# ATmega328p.net
KiCad netlist of a schematic drawn in Altium Designer
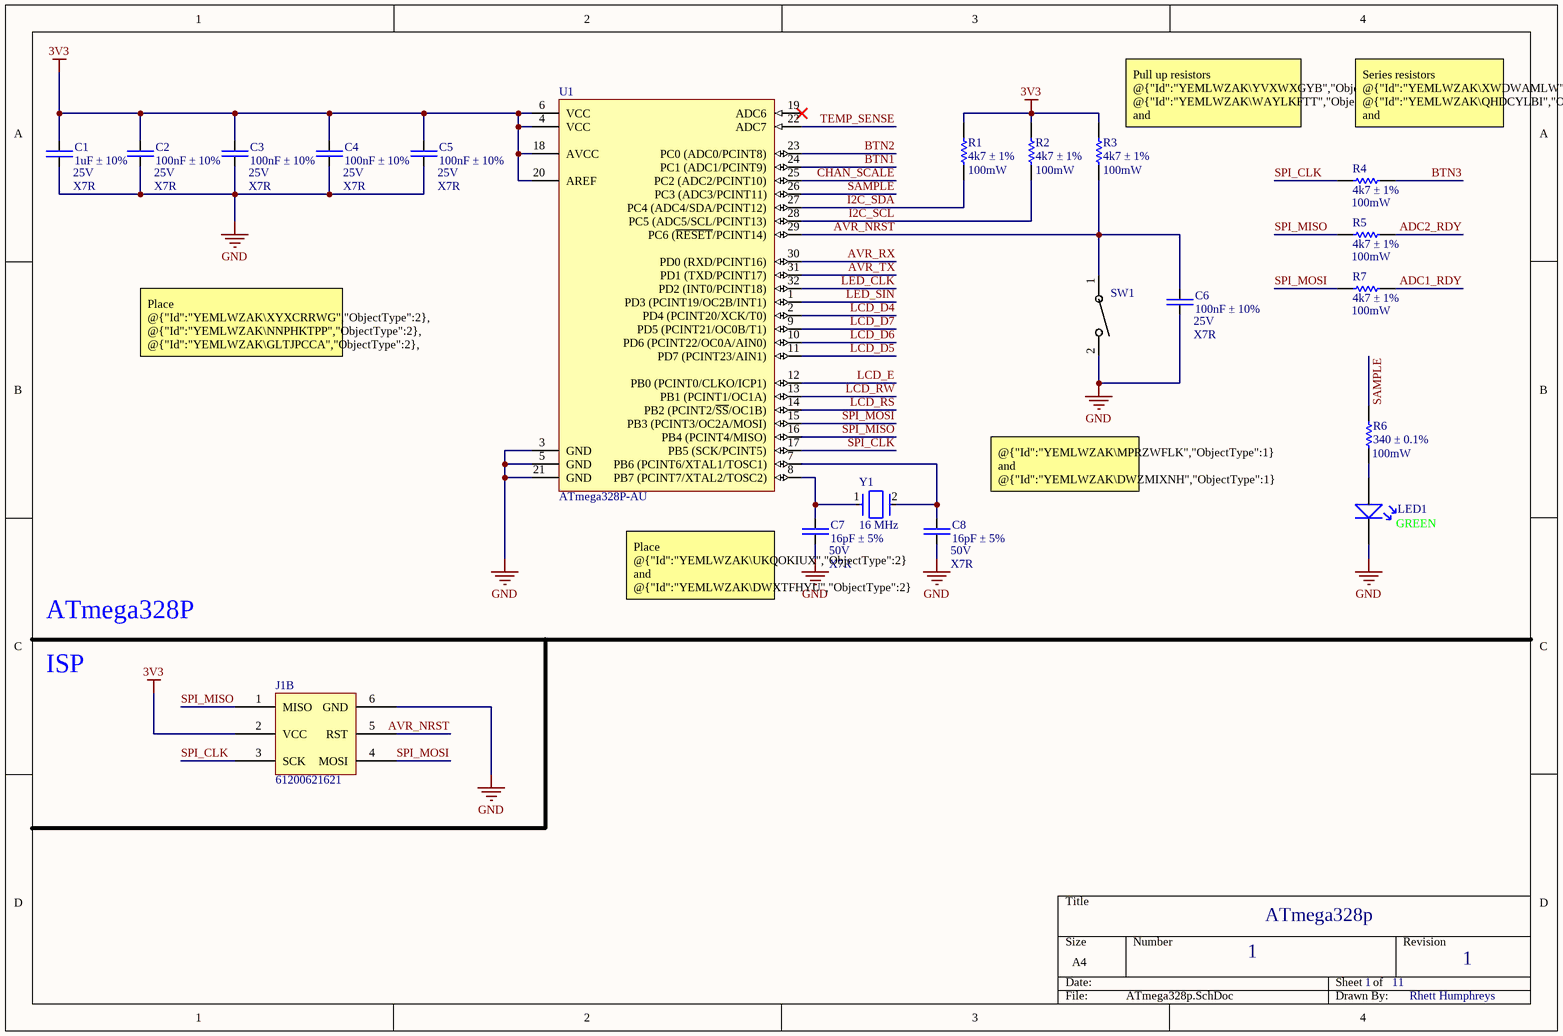
[diagram p0: ATmega328p.SchDoc]

(export (version "E")
  (design (tool "Eeschema 10.0.6"))
  (components
    (comp (ref "C1")
      (value "1uF ± 10%")
      (footprint "CAP-0805")
      (description "Capacitor chip unpolarized. 0603")
      (libsource (lib "Master") (part "CAP-0805"))
    )
    (comp (ref "C2")
      (value "100nF ± 10%")
      (footprint "CAP-0603")
      (description "Capacitor chip unpolarized. 0603")
      (libsource (lib "Master") (part "CAP-0603"))
    )
    (comp (ref "C3")
      (value "100nF ± 10%")
      (footprint "CAP-0603")
      (description "Capacitor chip unpolarized. 0603")
      (libsource (lib "Master") (part "CAP-0603"))
    )
    (comp (ref "C4")
      (value "100nF ± 10%")
      (footprint "CAP-0603")
      (description "Capacitor chip unpolarized. 0603")
      (libsource (lib "Master") (part "CAP-0603"))
    )
    (comp (ref "C5")
      (value "100nF ± 10%")
      (footprint "CAP-0603")
      (description "Capacitor chip unpolarized. 0603")
      (libsource (lib "Master") (part "CAP-0603"))
    )
    (comp (ref "C6")
      (value "100nF ± 10%")
      (footprint "CAP-0603")
      (description "Capacitor chip unpolarized. 0603")
      (libsource (lib "Master") (part "CAP-0603"))
    )
    (comp (ref "C7")
      (value "16pF ± 5%")
      (footprint "CAP-0603")
      (description "Capacitor chip unpolarized. 0603")
      (libsource (lib "Master") (part "CAP-0603"))
    )
    (comp (ref "C8")
      (value "16pF ± 5%")
      (footprint "CAP-0603")
      (description "Capacitor chip unpolarized. 0603")
      (libsource (lib "Master") (part "CAP-0603"))
    )
    (comp (ref "J1")
      (value "61200621621")
      (footprint "61200621621")
      (libsource (lib "Master") (part "61200621621"))
    )
    (comp (ref "LED1") (value "~") (footprint "0603 LED") (libsource (lib "Master") (part "0603 LED")))
    (comp (ref "R1")
      (value "4k7 ± 1%")
      (footprint "RES-0603")
      (description "Resistor chip. 0603")
      (libsource (lib "Master") (part "RES-0603"))
    )
    (comp (ref "R2")
      (value "4k7 ± 1%")
      (footprint "RES-0603")
      (description "Resistor chip. 0603")
      (libsource (lib "Master") (part "RES-0603"))
    )
    (comp (ref "R3")
      (value "4k7 ± 1%")
      (footprint "RES-0603")
      (description "Resistor chip. 0603")
      (libsource (lib "Master") (part "RES-0603"))
    )
    (comp (ref "R4")
      (value "4k7 ± 1%")
      (footprint "RES-0603")
      (description "Resistor chip. 0603")
      (libsource (lib "Master") (part "RES-0603"))
    )
    (comp (ref "R5")
      (value "4k7 ± 1%")
      (footprint "RES-0603")
      (description "Resistor chip. 0603")
      (libsource (lib "Master") (part "RES-0603"))
    )
    (comp (ref "R6")
      (value "340 ± 0.1%")
      (footprint "RES-0603")
      (description "Resistor chip. 0603")
      (libsource (lib "Master") (part "RES-0603"))
    )
    (comp (ref "R7")
      (value "4k7 ± 1%")
      (footprint "RES-0603")
      (description "Resistor chip. 0603")
      (libsource (lib "Master") (part "RES-0603"))
    )
    (comp (ref "SW1")
      (value "PTS636SK43JSMTRLFS")
      (footprint "SW_PTS636S-J_CNK")
      (description "No Description Available")
      (libsource (lib "Master") (part "PTS636SK43JSMTRLFS"))
    )
    (comp (ref "U1")
      (value "ATmega328P-AU")
      (footprint "32A_M")
      (libsource (lib "Altium Content Vault") (part "MC-8B-ATM48-SQ32"))
    )
    (comp (ref "Y1")
      (value "16 MHz")
      (footprint "FP-ABM7-MFG")
      (description "Crystal 16MHz ±20ppm 18pF SMD-2 6mm x 3.5mm")
      (fields (field (name "TOLERANCE") "20ppm"))
      (libsource (lib "Altium Content Vault") (part "c23a69dc6c9e2f18f2079038eb95dd1"))
    )
  )
  (nets
    (net (code "1") (name "/ADC1_RDY") (class "Default") (node (ref "R7") (pin "2") (pintype "passive")))
    (net (code "2") (name "/ADC2_RDY") (class "Default") (node (ref "R5") (pin "2") (pintype "passive")))
    (net (code "3") (name "/AVR_NRST") (class "Default")
      (node (ref "C6") (pin "2") (pintype "passive"))
      (node (ref "J1") (pin "5") (pinfunction "RST_5") (pintype "passive"))
      (node (ref "R3") (pin "2") (pintype "passive"))
      (node (ref "SW1") (pin "1") (pinfunction "1_1") (pintype "passive"))
      (node (ref "U1") (pin "29") (pinfunction "PC6_(~{RESET}/PCINT14)_29") (pintype "bidirectional"))
    )
    (net (code "4") (name "/AVR_RX") (class "Default")
      (node (ref "U1") (pin "30") (pinfunction "PD0_(RXD/PCINT16)_30") (pintype "bidirectional"))
    )
    (net (code "5") (name "/AVR_TX") (class "Default")
      (node (ref "U1") (pin "31") (pinfunction "PD1_(TXD/PCINT17)_31") (pintype "bidirectional"))
    )
    (net (code "6") (name "/BTN1") (class "Default")
      (node (ref "U1") (pin "24") (pinfunction "PC1_(ADC1/PCINT9)_24") (pintype "bidirectional"))
    )
    (net (code "7") (name "/BTN2") (class "Default")
      (node (ref "U1") (pin "23") (pinfunction "PC0_(ADC0/PCINT8)_23") (pintype "bidirectional"))
    )
    (net (code "8") (name "/BTN3") (class "Default") (node (ref "R4") (pin "2") (pintype "passive")))
    (net (code "9") (name "/CHAN_SCALE") (class "Default")
      (node (ref "U1") (pin "25") (pinfunction "PC2_(ADC2/PCINT10)_25") (pintype "bidirectional"))
    )
    (net (code "10") (name "/I2C_SCL") (class "Default")
      (node (ref "R2") (pin "2") (pintype "passive"))
      (node (ref "U1") (pin "28") (pinfunction "PC5_(ADC5/SCL/PCINT13)_28") (pintype "bidirectional"))
    )
    (net (code "11") (name "/I2C_SDA") (class "Default")
      (node (ref "R1") (pin "2") (pintype "passive"))
      (node (ref "U1") (pin "27") (pinfunction "PC4_(ADC4/SDA/PCINT12)_27") (pintype "bidirectional"))
    )
    (net (code "12") (name "/LCD_D4") (class "Default")
      (node (ref "U1") (pin "2") (pinfunction "PD4_(PCINT20/XCK/T0)_2") (pintype "bidirectional"))
    )
    (net (code "13") (name "/LCD_D5") (class "Default")
      (node (ref "U1") (pin "11") (pinfunction "PD7_(PCINT23/AIN1)_11") (pintype "bidirectional"))
    )
    (net (code "14") (name "/LCD_D6") (class "Default")
      (node (ref "U1") (pin "10") (pinfunction "PD6_(PCINT22/OC0A/AIN0)_10") (pintype "bidirectional"))
    )
    (net (code "15") (name "/LCD_D7") (class "Default")
      (node (ref "U1") (pin "9") (pinfunction "PD5_(PCINT21/OC0B/T1)_9") (pintype "bidirectional"))
    )
    (net (code "16") (name "/LCD_E") (class "Default")
      (node (ref "U1") (pin "12") (pinfunction "PB0_(PCINT0/CLKO/ICP1)_12") (pintype "bidirectional"))
    )
    (net (code "17") (name "/LCD_RS") (class "Default")
      (node (ref "U1") (pin "14") (pinfunction "PB2_(PCINT2/~{SS}/OC1B)_14") (pintype "bidirectional"))
    )
    (net (code "18") (name "/LCD_RW") (class "Default")
      (node (ref "U1") (pin "13") (pinfunction "PB1_(PCINT1/OC1A)_13") (pintype "bidirectional"))
    )
    (net (code "19") (name "/LED_CLK") (class "Default")
      (node (ref "U1") (pin "32") (pinfunction "PD2_(INT0/PCINT18)_32") (pintype "bidirectional"))
    )
    (net (code "20") (name "/LED_SIN") (class "Default")
      (node (ref "U1") (pin "1") (pinfunction "PD3_(PCINT19/OC2B/INT1)_1") (pintype "bidirectional"))
    )
    (net (code "21") (name "/SAMPLE") (class "Default")
      (node (ref "R6") (pin "1") (pintype "passive"))
      (node (ref "U1") (pin "26") (pinfunction "PC3_(ADC3/PCINT11)_26") (pintype "bidirectional"))
    )
    (net (code "22") (name "/SPI_CLK") (class "Default")
      (node (ref "J1") (pin "3") (pinfunction "SCK_3") (pintype "passive"))
      (node (ref "R4") (pin "1") (pintype "passive"))
      (node (ref "U1") (pin "17") (pinfunction "PB5_(SCK/PCINT5)_17") (pintype "bidirectional"))
    )
    (net (code "23") (name "/SPI_MISO") (class "Default")
      (node (ref "J1") (pin "1") (pinfunction "MISO_1") (pintype "passive"))
      (node (ref "R5") (pin "1") (pintype "passive"))
      (node (ref "U1") (pin "16") (pinfunction "PB4_(PCINT4/MISO)_16") (pintype "bidirectional"))
    )
    (net (code "24") (name "/SPI_MOSI") (class "Default")
      (node (ref "J1") (pin "4") (pinfunction "MOSI_4") (pintype "passive"))
      (node (ref "R7") (pin "1") (pintype "passive"))
      (node (ref "U1") (pin "15") (pinfunction "PB3_(PCINT3/OC2A/MOSI)_15") (pintype "bidirectional"))
    )
    (net (code "25") (name "/TEMP_SENSE") (class "Default")
      (node (ref "U1") (pin "22") (pinfunction "ADC7_22") (pintype "input"))
    )
    (net (code "26") (name "3V3") (class "Default")
      (node (ref "C1") (pin "2") (pintype "passive"))
      (node (ref "C2") (pin "2") (pintype "passive"))
      (node (ref "C3") (pin "2") (pintype "passive"))
      (node (ref "C4") (pin "2") (pintype "passive"))
      (node (ref "C5") (pin "2") (pintype "passive"))
      (node (ref "J1") (pin "2") (pinfunction "VCC_2") (pintype "passive"))
      (node (ref "R1") (pin "1") (pintype "passive"))
      (node (ref "R2") (pin "1") (pintype "passive"))
      (node (ref "R3") (pin "1") (pintype "passive"))
      (node (ref "U1") (pin "18") (pinfunction "AVCC_18") (pintype "power_in"))
      (node (ref "U1") (pin "20") (pinfunction "AREF_20") (pintype "passive"))
      (node (ref "U1") (pin "4") (pinfunction "VCC_4") (pintype "power_in"))
      (node (ref "U1") (pin "6") (pinfunction "VCC_6") (pintype "power_in"))
    )
    (net (code "27") (name "GND") (class "Default")
      (node (ref "C1") (pin "1") (pintype "passive"))
      (node (ref "C2") (pin "1") (pintype "passive"))
      (node (ref "C3") (pin "1") (pintype "passive"))
      (node (ref "C4") (pin "1") (pintype "passive"))
      (node (ref "C5") (pin "1") (pintype "passive"))
      (node (ref "C6") (pin "1") (pintype "passive"))
      (node (ref "C7") (pin "1") (pintype "passive"))
      (node (ref "C8") (pin "1") (pintype "passive"))
      (node (ref "J1") (pin "6") (pinfunction "GND_6") (pintype "passive"))
      (node (ref "LED1") (pin "2") (pinfunction "5_2") (pintype "passive"))
      (node (ref "SW1") (pin "2") (pinfunction "2_2") (pintype "passive"))
      (node (ref "U1") (pin "21") (pinfunction "GND_21") (pintype "power_in"))
      (node (ref "U1") (pin "3") (pinfunction "GND_3") (pintype "power_in"))
      (node (ref "U1") (pin "5") (pinfunction "GND_5") (pintype "power_in"))
    )
    (net (code "28") (name "Net-(LED1-6)") (class "Default")
      (node (ref "LED1") (pin "1") (pinfunction "6_1") (pintype "passive"))
      (node (ref "R6") (pin "2") (pintype "passive"))
    )
    (net (code "29") (name "Net-(U1-PB6_(PCINT6{slash}XTAL1{slash}TOSC1))") (class "Default")
      (node (ref "C8") (pin "2") (pintype "passive"))
      (node (ref "U1") (pin "7") (pinfunction "PB6_(PCINT6/XTAL1/TOSC1)_7") (pintype "bidirectional"))
      (node (ref "Y1") (pin "2") (pinfunction "2_2") (pintype "passive"))
    )
    (net (code "30") (name "Net-(U1-PB7_(PCINT7{slash}XTAL2{slash}TOSC2))") (class "Default")
      (node (ref "C7") (pin "2") (pintype "passive"))
      (node (ref "U1") (pin "8") (pinfunction "PB7_(PCINT7/XTAL2/TOSC2)_8") (pintype "bidirectional"))
      (node (ref "Y1") (pin "1") (pinfunction "1_1") (pintype "passive"))
    )
    (net (code "31") (name "unconnected-(U1-ADC6-Pad19)") (class "Default")
      (node (ref "U1") (pin "19") (pinfunction "ADC6_19") (pintype "input+no_connect"))
    )
  )
)
